# jphy_v1_3.net
KiCad netlist of a schematic drawn in EAGLE
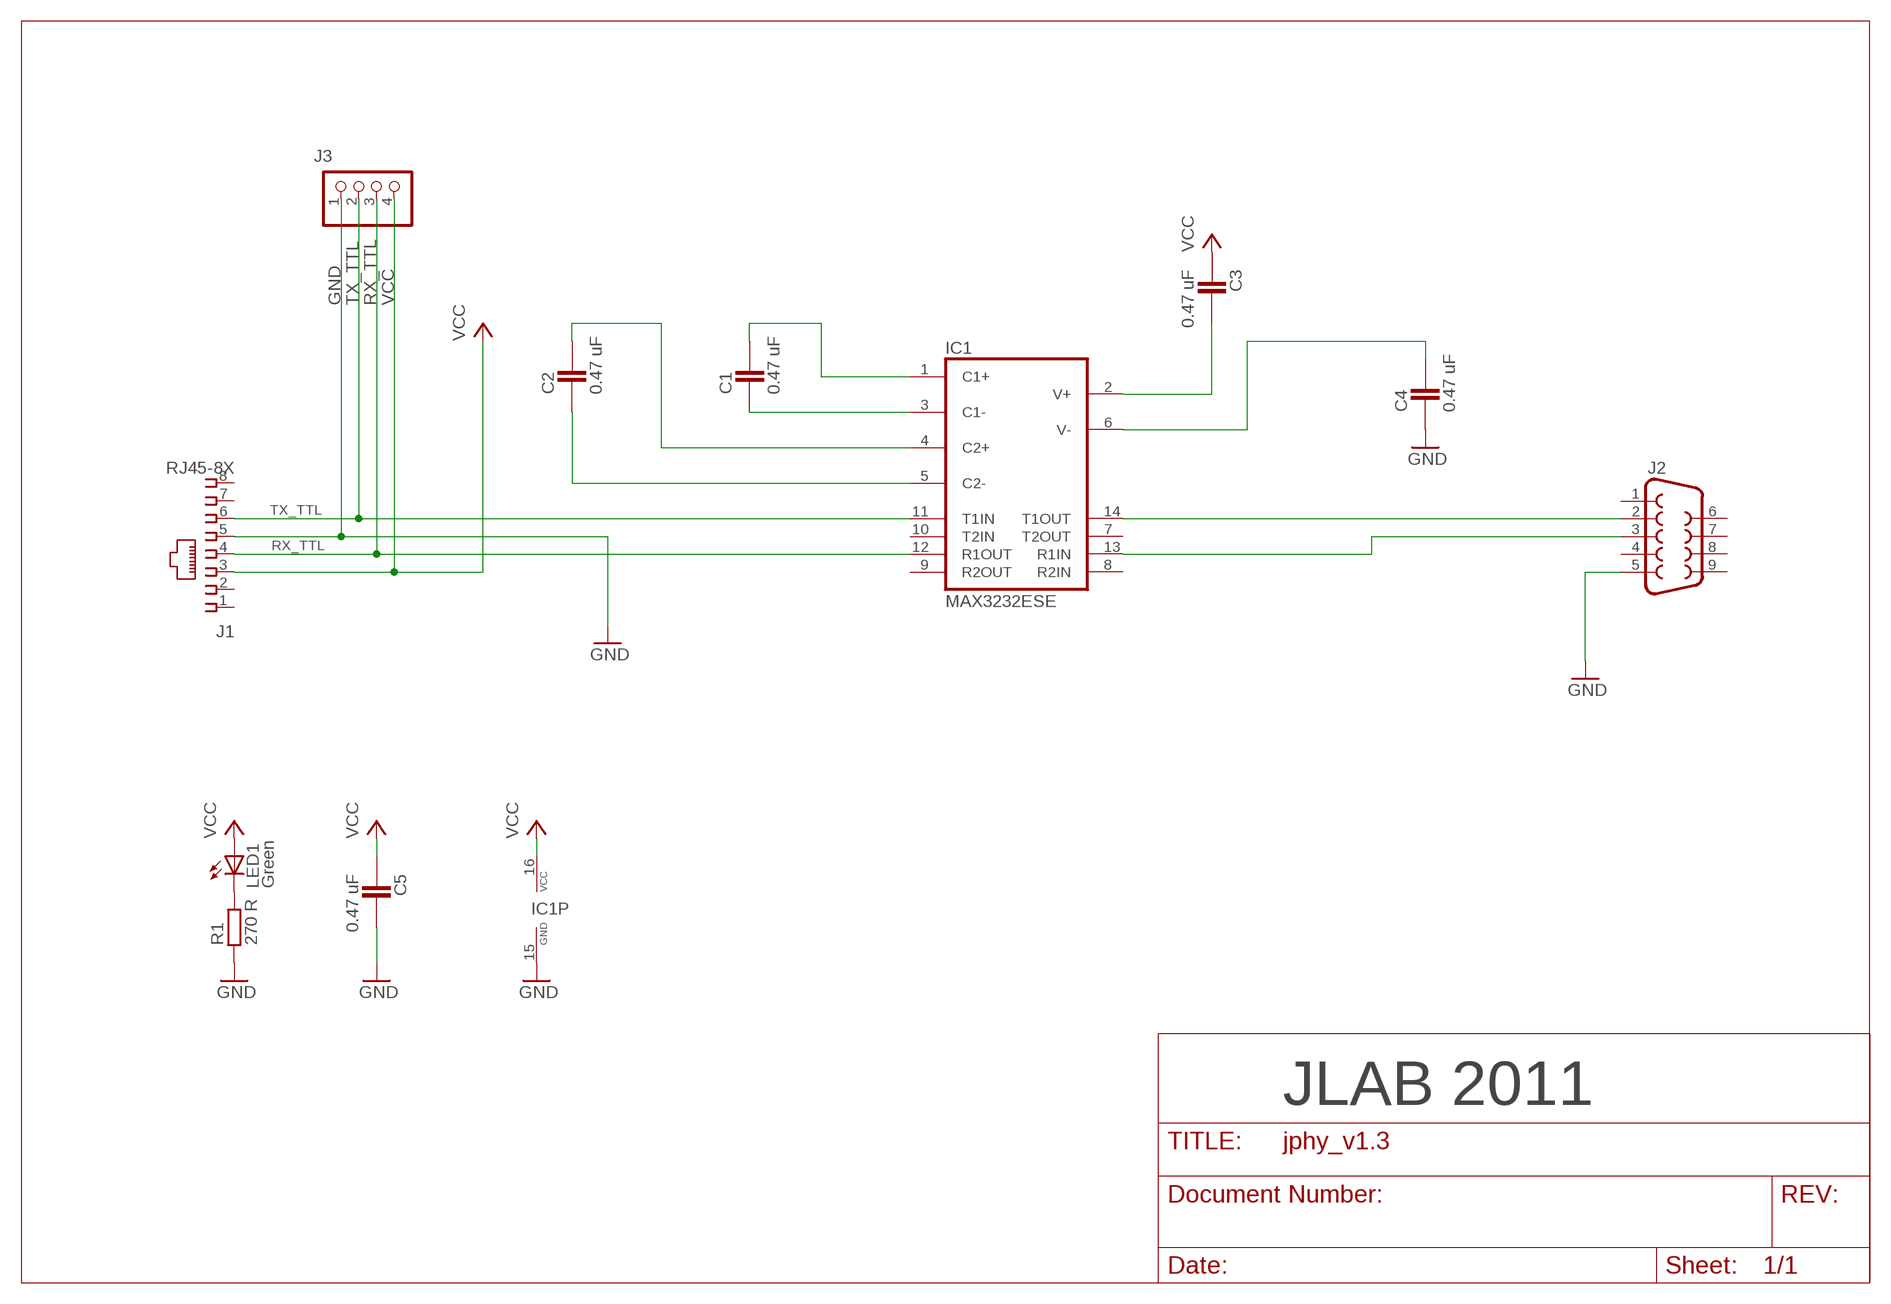
[diagram p0: schematic, sheet 1]

(export (version "E")
  (design (tool "Eeschema 10.0.6"))
  (components
    (comp (ref "C1")
      (value "0.47 uF")
      (footprint "eagle-import:CAPC2012X145AN")
      (libsource (lib "eagle-import") (part "CAPACITOR_0805"))
    )
    (comp (ref "C2")
      (value "0.47 uF")
      (footprint "eagle-import:CAPC2012X145AN")
      (libsource (lib "eagle-import") (part "CAPACITOR_0805"))
    )
    (comp (ref "C3")
      (value "0.47 uF")
      (footprint "eagle-import:CAPC2012X145AN")
      (libsource (lib "eagle-import") (part "CAPACITOR_0805"))
    )
    (comp (ref "C4")
      (value "0.47 uF")
      (footprint "eagle-import:CAPC2012X145AN")
      (libsource (lib "eagle-import") (part "CAPACITOR_0805"))
    )
    (comp (ref "C5")
      (value "0.47 uF")
      (footprint "eagle-import:CAPC2012X145AN")
      (libsource (lib "eagle-import") (part "CAPACITOR_0805"))
    )
    (comp (ref "IC1")
      (value "MAX3232ESE")
      (footprint "eagle-import:SO16")
      (fields (field (name "MF") "MAXIM"))
      (libsource (lib "eagle-import") (part "MAX3232SEE"))
    )
    (comp (ref "J1")
      (value "RJ45-8X")
      (footprint "eagle-import:RJ45-NO-SHIELD")
      (libsource (lib "eagle-import") (part "RJ45-8X"))
    )
    (comp (ref "J2")
      (value "F09D")
      (footprint "eagle-import:F09D")
      (libsource (lib "eagle-import") (part "F09D"))
    )
    (comp (ref "J3")
      (value "PINHD-1X4")
      (footprint "eagle-import:1X04")
      (libsource (lib "eagle-import") (part "PINHD-1X4"))
    )
    (comp (ref "LED1")
      (value "Green")
      (footprint "eagle-import:CHIP-LED0805")
      (libsource (lib "eagle-import") (part "LEDCHIP-LED0805"))
    )
    (comp (ref "R1")
      (value "270 R")
      (footprint "eagle-import:RESC2012X70N")
      (libsource (lib "eagle-import") (part "RESISTOR_0805"))
    )
  )
  (nets
    (net (code "1") (name "/RX_TTL") (class "Default")
      (node (ref "IC1") (pin "12") (pinfunction "R1OUT_12") (pintype "output"))
      (node (ref "J1") (pin "4") (pinfunction "4_4") (pintype "passive"))
      (node (ref "J3") (pin "3") (pinfunction "3_3") (pintype "passive"))
    )
    (net (code "2") (name "/TX_TTL") (class "Default")
      (node (ref "IC1") (pin "11") (pinfunction "T1IN_11") (pintype "input"))
      (node (ref "J1") (pin "6") (pinfunction "6_6") (pintype "passive"))
      (node (ref "J3") (pin "2") (pinfunction "2_2") (pintype "passive"))
    )
    (net (code "3") (name "GND") (class "Default")
      (node (ref "C4") (pin "1") (pinfunction "1_1") (pintype "passive"))
      (node (ref "C5") (pin "2") (pinfunction "2_2") (pintype "passive"))
      (node (ref "IC1") (pin "15") (pinfunction "GND_15") (pintype "power_in"))
      (node (ref "J1") (pin "5") (pinfunction "5_5") (pintype "passive"))
      (node (ref "J2") (pin "5") (pinfunction "5_5") (pintype "passive"))
      (node (ref "J3") (pin "1") (pinfunction "1_1") (pintype "passive"))
      (node (ref "R1") (pin "1") (pinfunction "1_1") (pintype "passive"))
    )
    (net (code "4") (name "Net-(IC1A-C1+)") (class "Default")
      (node (ref "C1") (pin "2") (pinfunction "2_2") (pintype "passive"))
      (node (ref "IC1") (pin "1") (pinfunction "C1+_1") (pintype "bidirectional"))
    )
    (net (code "5") (name "Net-(IC1A-C1-)") (class "Default")
      (node (ref "C1") (pin "1") (pinfunction "1_1") (pintype "passive"))
      (node (ref "IC1") (pin "3") (pinfunction "C1-_3") (pintype "bidirectional"))
    )
    (net (code "6") (name "Net-(IC1A-C2+)") (class "Default")
      (node (ref "C2") (pin "2") (pinfunction "2_2") (pintype "passive"))
      (node (ref "IC1") (pin "4") (pinfunction "C2+_4") (pintype "bidirectional"))
    )
    (net (code "7") (name "Net-(IC1A-C2-)") (class "Default")
      (node (ref "C2") (pin "1") (pinfunction "1_1") (pintype "passive"))
      (node (ref "IC1") (pin "5") (pinfunction "C2-_5") (pintype "bidirectional"))
    )
    (net (code "8") (name "Net-(IC1A-R1IN)") (class "Default")
      (node (ref "IC1") (pin "13") (pinfunction "R1IN_13") (pintype "input"))
      (node (ref "J2") (pin "3") (pinfunction "3_3") (pintype "passive"))
    )
    (net (code "9") (name "Net-(IC1A-T1OUT)") (class "Default")
      (node (ref "IC1") (pin "14") (pinfunction "T1OUT_14") (pintype "output"))
      (node (ref "J2") (pin "2") (pinfunction "2_2") (pintype "passive"))
    )
    (net (code "10") (name "Net-(IC1A-V+)") (class "Default")
      (node (ref "C3") (pin "2") (pinfunction "2_2") (pintype "passive"))
      (node (ref "IC1") (pin "2") (pinfunction "V+_2") (pintype "bidirectional"))
    )
    (net (code "11") (name "Net-(IC1A-V-)") (class "Default")
      (node (ref "C4") (pin "2") (pinfunction "2_2") (pintype "passive"))
      (node (ref "IC1") (pin "6") (pinfunction "V-_6") (pintype "bidirectional"))
    )
    (net (code "12") (name "Net-(LED1-PadC)") (class "Default")
      (node (ref "LED1") (pin "C") (pinfunction "C_C") (pintype "passive"))
      (node (ref "R1") (pin "2") (pinfunction "2_2") (pintype "passive"))
    )
    (net (code "13") (name "VCC") (class "Default")
      (node (ref "C3") (pin "1") (pinfunction "1_1") (pintype "passive"))
      (node (ref "C5") (pin "1") (pinfunction "1_1") (pintype "passive"))
      (node (ref "IC1") (pin "16") (pinfunction "VCC_16") (pintype "power_in"))
      (node (ref "J1") (pin "3") (pinfunction "3_3") (pintype "passive"))
      (node (ref "J3") (pin "4") (pinfunction "4_4") (pintype "passive"))
      (node (ref "LED1") (pin "A") (pinfunction "A_A") (pintype "passive"))
    )
    (net (code "14") (name "unconnected-(IC1A-R2IN-Pad8)") (class "Default")
      (node (ref "IC1") (pin "8") (pinfunction "R2IN_8") (pintype "input"))
    )
    (net (code "15") (name "unconnected-(IC1A-R2OUT-Pad9)") (class "Default")
      (node (ref "IC1") (pin "9") (pinfunction "R2OUT_9") (pintype "output"))
    )
    (net (code "16") (name "unconnected-(IC1A-T2IN-Pad10)") (class "Default")
      (node (ref "IC1") (pin "10") (pinfunction "T2IN_10") (pintype "input"))
    )
    (net (code "17") (name "unconnected-(IC1A-T2OUT-Pad7)") (class "Default")
      (node (ref "IC1") (pin "7") (pinfunction "T2OUT_7") (pintype "output"))
    )
    (net (code "18") (name "unconnected-(J1-Pad1)") (class "Default")
      (node (ref "J1") (pin "1") (pinfunction "1_1") (pintype "passive"))
    )
    (net (code "19") (name "unconnected-(J1-Pad2)") (class "Default")
      (node (ref "J1") (pin "2") (pinfunction "2_2") (pintype "passive"))
    )
    (net (code "20") (name "unconnected-(J1-Pad7)") (class "Default")
      (node (ref "J1") (pin "7") (pinfunction "7_7") (pintype "passive"))
    )
    (net (code "21") (name "unconnected-(J1-Pad8)") (class "Default")
      (node (ref "J1") (pin "8") (pinfunction "8_8") (pintype "passive"))
    )
    (net (code "22") (name "unconnected-(J2-Pad1)") (class "Default")
      (node (ref "J2") (pin "1") (pinfunction "1_1") (pintype "passive"))
    )
    (net (code "23") (name "unconnected-(J2-Pad4)") (class "Default")
      (node (ref "J2") (pin "4") (pinfunction "4_4") (pintype "passive"))
    )
    (net (code "24") (name "unconnected-(J2-Pad6)") (class "Default")
      (node (ref "J2") (pin "6") (pinfunction "6_6") (pintype "passive"))
    )
    (net (code "25") (name "unconnected-(J2-Pad7)") (class "Default")
      (node (ref "J2") (pin "7") (pinfunction "7_7") (pintype "passive"))
    )
    (net (code "26") (name "unconnected-(J2-Pad8)") (class "Default")
      (node (ref "J2") (pin "8") (pinfunction "8_8") (pintype "passive"))
    )
    (net (code "27") (name "unconnected-(J2-Pad9)") (class "Default")
      (node (ref "J2") (pin "9") (pinfunction "9_9") (pintype "passive"))
    )
  )
)
